# FK723MK1_ZGT6_DSUB_Driver.net
KiCad netlist of a schematic drawn in Altium Designer
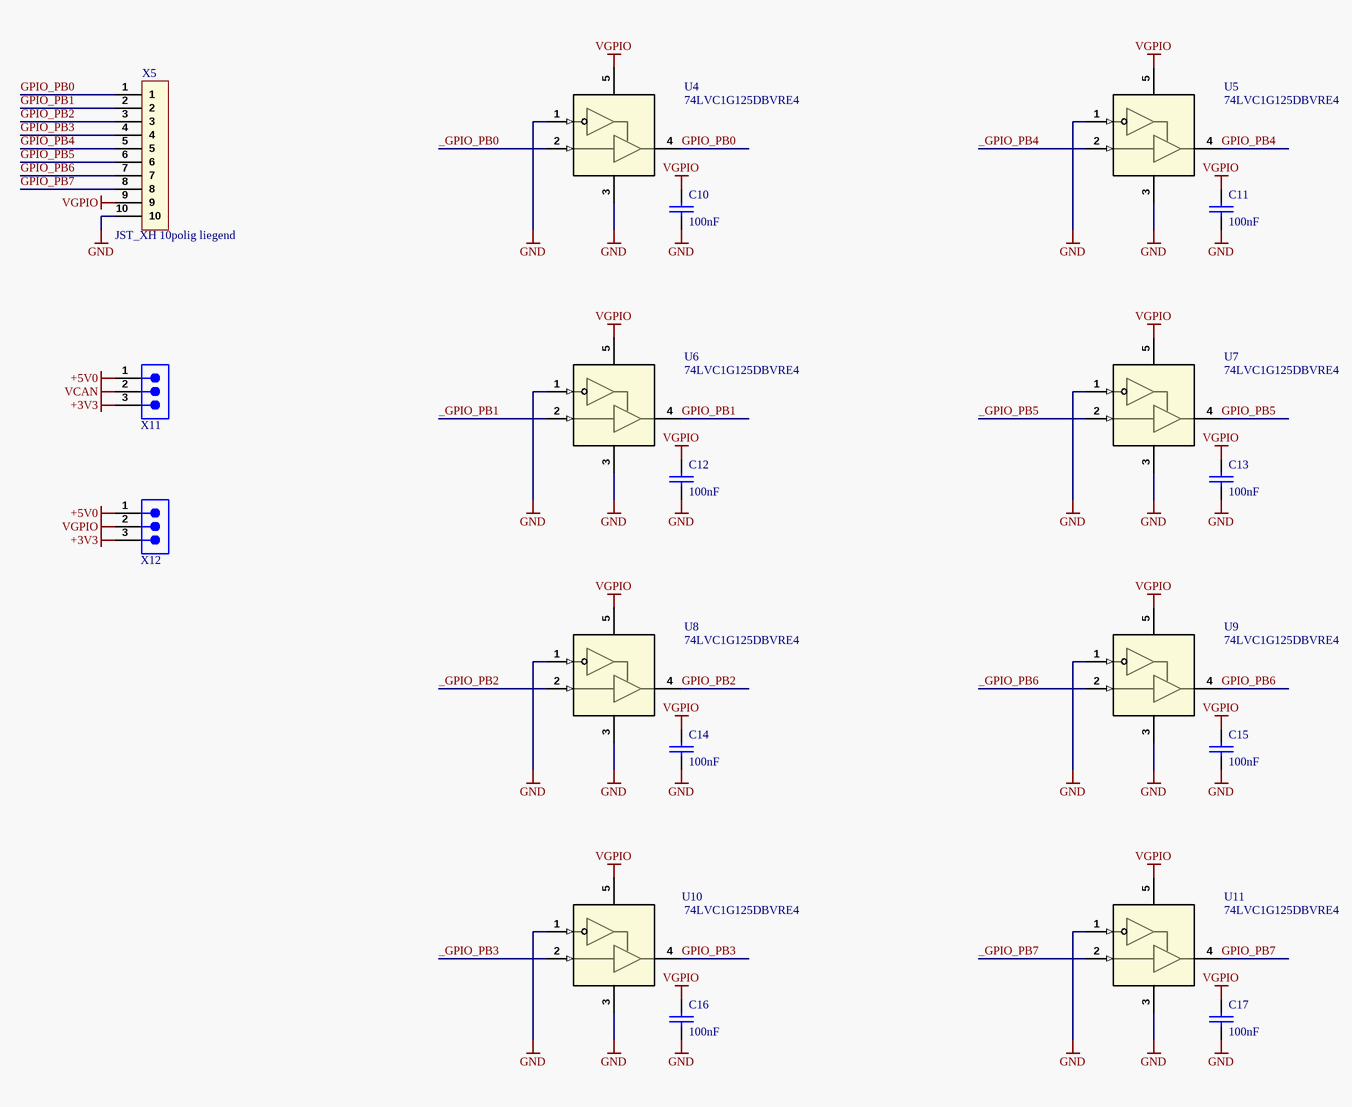
[diagram p0: FK723MK1_ZGT6_DSUB_Driver.SchDoc]

(export (version "E")
  (design (tool "Eeschema 10.0.6"))
  (components
    (comp (ref "C10")
      (value "100nF")
      (footprint "0402")
      (description "100nF 16V 10% 0402")
      (libsource (lib "ChipCapacitors") (part "100nF"))
    )
    (comp (ref "C11")
      (value "100nF")
      (footprint "0402")
      (description "100nF 16V 10% 0402")
      (libsource (lib "ChipCapacitors") (part "100nF"))
    )
    (comp (ref "C12")
      (value "100nF")
      (footprint "0402")
      (description "100nF 16V 10% 0402")
      (libsource (lib "ChipCapacitors") (part "100nF"))
    )
    (comp (ref "C13")
      (value "100nF")
      (footprint "0402")
      (description "100nF 16V 10% 0402")
      (libsource (lib "ChipCapacitors") (part "100nF"))
    )
    (comp (ref "C14")
      (value "100nF")
      (footprint "0402")
      (description "100nF 16V 10% 0402")
      (libsource (lib "ChipCapacitors") (part "100nF"))
    )
    (comp (ref "C15")
      (value "100nF")
      (footprint "0402")
      (description "100nF 16V 10% 0402")
      (libsource (lib "ChipCapacitors") (part "100nF"))
    )
    (comp (ref "C16")
      (value "100nF")
      (footprint "0402")
      (description "100nF 16V 10% 0402")
      (libsource (lib "ChipCapacitors") (part "100nF"))
    )
    (comp (ref "C17")
      (value "100nF")
      (footprint "0402")
      (description "100nF 16V 10% 0402")
      (libsource (lib "ChipCapacitors") (part "100nF"))
    )
    (comp (ref "U4")
      (value "74LVC1G125DBVRE4")
      (footprint "DBV0005A_L")
      (description "Single 1.65-V to 5.5-V buffer with 3-state outputs 5-SOT-23 -40 to 125")
      (fields (field (name "COPYRIGHT") "Copyright (C) 2025 Ultra Librarian. All rights reserved."))
      (libsource (lib "74LVC1G125DBVRE4") (part "74LVC1G125DBVRE4"))
    )
    (comp (ref "U5")
      (value "74LVC1G125DBVRE4")
      (footprint "DBV0005A_L")
      (description "Single 1.65-V to 5.5-V buffer with 3-state outputs 5-SOT-23 -40 to 125")
      (fields (field (name "COPYRIGHT") "Copyright (C) 2025 Ultra Librarian. All rights reserved."))
      (libsource (lib "74LVC1G125DBVRE4") (part "74LVC1G125DBVRE4"))
    )
    (comp (ref "U6")
      (value "74LVC1G125DBVRE4")
      (footprint "DBV0005A_L")
      (description "Single 1.65-V to 5.5-V buffer with 3-state outputs 5-SOT-23 -40 to 125")
      (fields (field (name "COPYRIGHT") "Copyright (C) 2025 Ultra Librarian. All rights reserved."))
      (libsource (lib "74LVC1G125DBVRE4") (part "74LVC1G125DBVRE4"))
    )
    (comp (ref "U7")
      (value "74LVC1G125DBVRE4")
      (footprint "DBV0005A_L")
      (description "Single 1.65-V to 5.5-V buffer with 3-state outputs 5-SOT-23 -40 to 125")
      (fields (field (name "COPYRIGHT") "Copyright (C) 2025 Ultra Librarian. All rights reserved."))
      (libsource (lib "74LVC1G125DBVRE4") (part "74LVC1G125DBVRE4"))
    )
    (comp (ref "U8")
      (value "74LVC1G125DBVRE4")
      (footprint "DBV0005A_L")
      (description "Single 1.65-V to 5.5-V buffer with 3-state outputs 5-SOT-23 -40 to 125")
      (fields (field (name "COPYRIGHT") "Copyright (C) 2025 Ultra Librarian. All rights reserved."))
      (libsource (lib "74LVC1G125DBVRE4") (part "74LVC1G125DBVRE4"))
    )
    (comp (ref "U9")
      (value "74LVC1G125DBVRE4")
      (footprint "DBV0005A_L")
      (description "Single 1.65-V to 5.5-V buffer with 3-state outputs 5-SOT-23 -40 to 125")
      (fields (field (name "COPYRIGHT") "Copyright (C) 2025 Ultra Librarian. All rights reserved."))
      (libsource (lib "74LVC1G125DBVRE4") (part "74LVC1G125DBVRE4"))
    )
    (comp (ref "U10")
      (value "74LVC1G125DBVRE4")
      (footprint "DBV0005A_L")
      (description "Single 1.65-V to 5.5-V buffer with 3-state outputs 5-SOT-23 -40 to 125")
      (fields (field (name "COPYRIGHT") "Copyright (C) 2025 Ultra Librarian. All rights reserved."))
      (libsource (lib "74LVC1G125DBVRE4") (part "74LVC1G125DBVRE4"))
    )
    (comp (ref "U11")
      (value "74LVC1G125DBVRE4")
      (footprint "DBV0005A_L")
      (description "Single 1.65-V to 5.5-V buffer with 3-state outputs 5-SOT-23 -40 to 125")
      (fields (field (name "COPYRIGHT") "Copyright (C) 2025 Ultra Librarian. All rights reserved."))
      (libsource (lib "74LVC1G125DBVRE4") (part "74LVC1G125DBVRE4"))
    )
    (comp (ref "X5")
      (value "JST_XH 10polig liegend")
      (footprint "JST_XH 10polig, liegend")
      (libsource (lib "JST_XH") (part "JST_XH 10polig"))
    )
    (comp (ref "X11")
      (value "61300311121")
      (footprint "61300311121")
      (description "WR-PHD Pin Header, THT, Vertical, pitch 2.54mm, 1 Row, 3P")
      (fields (field (name "MANUFACTURER") "Wurth Elektronik"))
      (libsource (lib "Altium_WR-PHD (rev24a)") (part "61300311121"))
    )
    (comp (ref "X12")
      (value "61300311121")
      (footprint "61300311121")
      (description "WR-PHD Pin Header, THT, Vertical, pitch 2.54mm, 1 Row, 3P")
      (fields (field (name "MANUFACTURER") "Wurth Elektronik"))
      (libsource (lib "Altium_WR-PHD (rev24a)") (part "61300311121"))
    )
  )
  (nets
    (net (code "1") (name "+3V3") (class "Default")
      (node (ref "X11") (pin "3") (pinfunction "3_3") (pintype "passive"))
      (node (ref "X12") (pin "3") (pinfunction "3_3") (pintype "passive"))
    )
    (net (code "2") (name "+5V0") (class "Default")
      (node (ref "X11") (pin "1") (pinfunction "1_1") (pintype "passive"))
      (node (ref "X12") (pin "1") (pinfunction "1_1") (pintype "passive"))
    )
    (net (code "3") (name "/GPIO_PB0") (class "Default")
      (node (ref "U4") (pin "4") (pinfunction "Y_4") (pintype "tri_state"))
      (node (ref "X5") (pin "1") (pinfunction "1_1") (pintype "passive"))
    )
    (net (code "4") (name "/GPIO_PB1") (class "Default")
      (node (ref "U6") (pin "4") (pinfunction "Y_4") (pintype "tri_state"))
      (node (ref "X5") (pin "2") (pinfunction "2_2") (pintype "passive"))
    )
    (net (code "5") (name "/GPIO_PB2") (class "Default")
      (node (ref "U8") (pin "4") (pinfunction "Y_4") (pintype "tri_state"))
      (node (ref "X5") (pin "3") (pinfunction "3_3") (pintype "passive"))
    )
    (net (code "6") (name "/GPIO_PB3") (class "Default")
      (node (ref "U10") (pin "4") (pinfunction "Y_4") (pintype "tri_state"))
      (node (ref "X5") (pin "4") (pinfunction "4_4") (pintype "passive"))
    )
    (net (code "7") (name "/GPIO_PB4") (class "Default")
      (node (ref "U5") (pin "4") (pinfunction "Y_4") (pintype "tri_state"))
      (node (ref "X5") (pin "5") (pinfunction "5_5") (pintype "passive"))
    )
    (net (code "8") (name "/GPIO_PB5") (class "Default")
      (node (ref "U7") (pin "4") (pinfunction "Y_4") (pintype "tri_state"))
      (node (ref "X5") (pin "6") (pinfunction "6_6") (pintype "passive"))
    )
    (net (code "9") (name "/GPIO_PB6") (class "Default")
      (node (ref "U9") (pin "4") (pinfunction "Y_4") (pintype "tri_state"))
      (node (ref "X5") (pin "7") (pinfunction "7_7") (pintype "passive"))
    )
    (net (code "10") (name "/GPIO_PB7") (class "Default")
      (node (ref "U11") (pin "4") (pinfunction "Y_4") (pintype "tri_state"))
      (node (ref "X5") (pin "8") (pinfunction "8_8") (pintype "passive"))
    )
    (net (code "11") (name "/_GPIO_PB0") (class "Default")
      (node (ref "U4") (pin "2") (pinfunction "A_2") (pintype "input"))
    )
    (net (code "12") (name "/_GPIO_PB1") (class "Default")
      (node (ref "U6") (pin "2") (pinfunction "A_2") (pintype "input"))
    )
    (net (code "13") (name "/_GPIO_PB2") (class "Default")
      (node (ref "U8") (pin "2") (pinfunction "A_2") (pintype "input"))
    )
    (net (code "14") (name "/_GPIO_PB3") (class "Default")
      (node (ref "U10") (pin "2") (pinfunction "A_2") (pintype "input"))
    )
    (net (code "15") (name "/_GPIO_PB4") (class "Default")
      (node (ref "U5") (pin "2") (pinfunction "A_2") (pintype "input"))
    )
    (net (code "16") (name "/_GPIO_PB5") (class "Default")
      (node (ref "U7") (pin "2") (pinfunction "A_2") (pintype "input"))
    )
    (net (code "17") (name "/_GPIO_PB6") (class "Default")
      (node (ref "U9") (pin "2") (pinfunction "A_2") (pintype "input"))
    )
    (net (code "18") (name "/_GPIO_PB7") (class "Default")
      (node (ref "U11") (pin "2") (pinfunction "A_2") (pintype "input"))
    )
    (net (code "19") (name "GND") (class "Default")
      (node (ref "C10") (pin "2") (pinfunction "2_2") (pintype "passive"))
      (node (ref "C11") (pin "2") (pinfunction "2_2") (pintype "passive"))
      (node (ref "C12") (pin "2") (pinfunction "2_2") (pintype "passive"))
      (node (ref "C13") (pin "2") (pinfunction "2_2") (pintype "passive"))
      (node (ref "C14") (pin "2") (pinfunction "2_2") (pintype "passive"))
      (node (ref "C15") (pin "2") (pinfunction "2_2") (pintype "passive"))
      (node (ref "C16") (pin "2") (pinfunction "2_2") (pintype "passive"))
      (node (ref "C17") (pin "2") (pinfunction "2_2") (pintype "passive"))
      (node (ref "U10") (pin "1") (pinfunction "OE_N_1") (pintype "input"))
      (node (ref "U10") (pin "3") (pinfunction "GND_3") (pintype "power_in"))
      (node (ref "U11") (pin "1") (pinfunction "OE_N_1") (pintype "input"))
      (node (ref "U11") (pin "3") (pinfunction "GND_3") (pintype "power_in"))
      (node (ref "U4") (pin "1") (pinfunction "OE_N_1") (pintype "input"))
      (node (ref "U4") (pin "3") (pinfunction "GND_3") (pintype "power_in"))
      (node (ref "U5") (pin "1") (pinfunction "OE_N_1") (pintype "input"))
      (node (ref "U5") (pin "3") (pinfunction "GND_3") (pintype "power_in"))
      (node (ref "U6") (pin "1") (pinfunction "OE_N_1") (pintype "input"))
      (node (ref "U6") (pin "3") (pinfunction "GND_3") (pintype "power_in"))
      (node (ref "U7") (pin "1") (pinfunction "OE_N_1") (pintype "input"))
      (node (ref "U7") (pin "3") (pinfunction "GND_3") (pintype "power_in"))
      (node (ref "U8") (pin "1") (pinfunction "OE_N_1") (pintype "input"))
      (node (ref "U8") (pin "3") (pinfunction "GND_3") (pintype "power_in"))
      (node (ref "U9") (pin "1") (pinfunction "OE_N_1") (pintype "input"))
      (node (ref "U9") (pin "3") (pinfunction "GND_3") (pintype "power_in"))
      (node (ref "X5") (pin "10") (pinfunction "10_10") (pintype "passive"))
    )
    (net (code "20") (name "VCAN") (class "Default")
      (node (ref "X11") (pin "2") (pinfunction "2_2") (pintype "passive"))
    )
    (net (code "21") (name "VGPIO") (class "Default")
      (node (ref "C10") (pin "1") (pinfunction "1_1") (pintype "passive"))
      (node (ref "C11") (pin "1") (pinfunction "1_1") (pintype "passive"))
      (node (ref "C12") (pin "1") (pinfunction "1_1") (pintype "passive"))
      (node (ref "C13") (pin "1") (pinfunction "1_1") (pintype "passive"))
      (node (ref "C14") (pin "1") (pinfunction "1_1") (pintype "passive"))
      (node (ref "C15") (pin "1") (pinfunction "1_1") (pintype "passive"))
      (node (ref "C16") (pin "1") (pinfunction "1_1") (pintype "passive"))
      (node (ref "C17") (pin "1") (pinfunction "1_1") (pintype "passive"))
      (node (ref "U10") (pin "5") (pinfunction "VCC_5") (pintype "power_in"))
      (node (ref "U11") (pin "5") (pinfunction "VCC_5") (pintype "power_in"))
      (node (ref "U4") (pin "5") (pinfunction "VCC_5") (pintype "power_in"))
      (node (ref "U5") (pin "5") (pinfunction "VCC_5") (pintype "power_in"))
      (node (ref "U6") (pin "5") (pinfunction "VCC_5") (pintype "power_in"))
      (node (ref "U7") (pin "5") (pinfunction "VCC_5") (pintype "power_in"))
      (node (ref "U8") (pin "5") (pinfunction "VCC_5") (pintype "power_in"))
      (node (ref "U9") (pin "5") (pinfunction "VCC_5") (pintype "power_in"))
      (node (ref "X12") (pin "2") (pinfunction "2_2") (pintype "passive"))
      (node (ref "X5") (pin "9") (pinfunction "9_9") (pintype "passive"))
    )
  )
)
